# DMX.net
KiCad netlist of a schematic drawn in Altium Designer
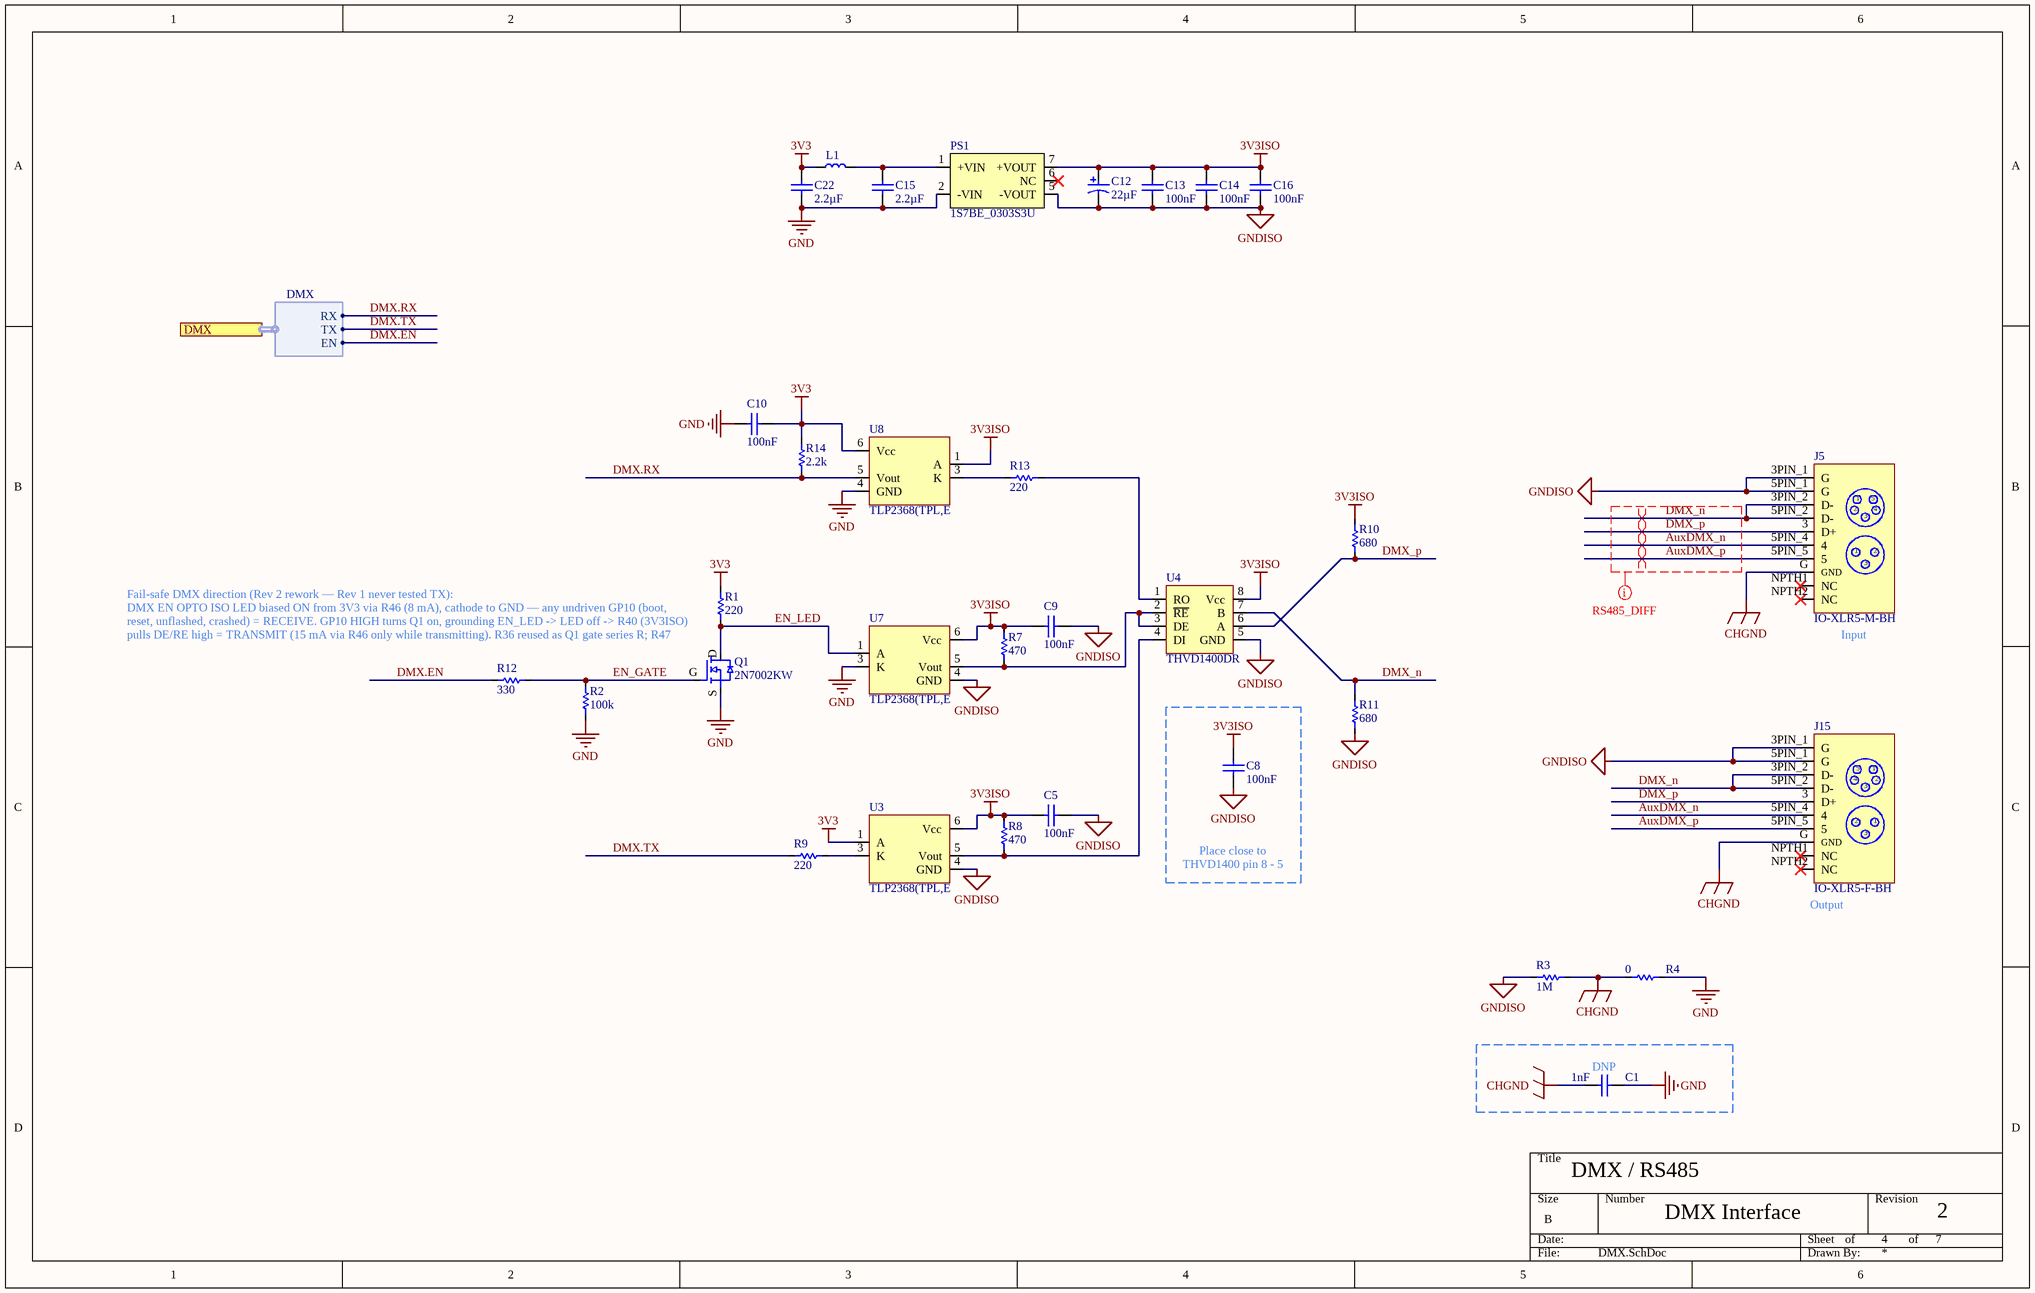
[diagram p0: DMX.SchDoc]

(export (version "E")
  (design (tool "Eeschema 10.0.6"))
  (components
    (comp (ref "C1")
      (value "1nF")
      (footprint "CAPC1608X10N_0603_MED")
      (fields (field (name "TOLERANCE") "10%") (field (name "Comment") "C0603C102K5RACTU"))
      (libsource (lib "Equus Computer Systems") (part "CAP-NP-2"))
    )
    (comp (ref "C5")
      (value "100nF")
      (footprint "CAPC1608X10N_0603_MED")
      (fields (field (name "Comment") "CC0603KRX7R0BB104"))
      (libsource (lib "Equus Computer Systems") (part "CAP-NP-2"))
    )
    (comp (ref "C8")
      (value "100nF")
      (footprint "CAPC1608X10N_0603_MED")
      (fields (field (name "Comment") "CC0603KRX7R0BB104"))
      (libsource (lib "Equus Computer Systems") (part "CAP-NP-2"))
    )
    (comp (ref "C9")
      (value "100nF")
      (footprint "CAPC1608X10N_0603_MED")
      (fields (field (name "Comment") "CC0603KRX7R0BB104"))
      (libsource (lib "Equus Computer Systems") (part "CAP-NP-2"))
    )
    (comp (ref "C10")
      (value "100nF")
      (footprint "CAPC1608X10N_0603_MED")
      (fields (field (name "Comment") "CC0603KRX7R0BB104"))
      (libsource (lib "Equus Computer Systems") (part "CAP-NP-2"))
    )
    (comp (ref "C12")
      (value "22µF")
      (footprint "CAPCP3528X21N_1210_1411_MED")
      (fields (field (name "TOLERANCE") "10%") (field (name "Comment") "TPSB226K010R0500"))
      (libsource (lib "Equus Computer Systems") (part "CAP-P-2"))
    )
    (comp (ref "C13")
      (value "100nF")
      (footprint "CAPC1608X10N_0603_MED")
      (fields (field (name "Comment") "CC0603KRX7R0BB104"))
      (libsource (lib "Equus Computer Systems") (part "CAP-NP-2"))
    )
    (comp (ref "C14")
      (value "100nF")
      (footprint "CAPC1608X10N_0603_MED")
      (fields (field (name "Comment") "CC0603KRX7R0BB104"))
      (libsource (lib "Equus Computer Systems") (part "CAP-NP-2"))
    )
    (comp (ref "C15")
      (value "2.2µF")
      (footprint "CAPC2012X14N_0805_MED")
      (description "Ceramic Capacitor, Multilayer, Ceramic, 2.2uF, 50V, 10%, X6S, 0805")
      (fields (field (name "TOLERANCE") "10%") (field (name "Comment") "CGA4J3X7R1H225K125AE"))
      (libsource (lib "Equus Computer Systems") (part "CAP-NP-2"))
    )
    (comp (ref "C16")
      (value "100nF")
      (footprint "CAPC1608X10N_0603_MED")
      (fields (field (name "Comment") "CC0603KRX7R0BB104"))
      (libsource (lib "Equus Computer Systems") (part "CAP-NP-2"))
    )
    (comp (ref "C22")
      (value "2.2µF")
      (footprint "CAPC2012X14N_0805_MED")
      (description "Ceramic Capacitor, Multilayer, Ceramic, 2.2uF, 50V, 10%, X6S, 0805")
      (fields (field (name "TOLERANCE") "10%") (field (name "Comment") "CGA4J3X7R1H225K125AE"))
      (libsource (lib "Equus Computer Systems") (part "CAP-NP-2"))
    )
    (comp (ref "J5")
      (value "IO-XLR5-M-BH")
      (footprint "IO-XLR5-M-BH-Footprint-1")
      (description "B Series, 5 Pin XLR, Male, Horizontal Pcb Mount With Separate Ground Pin")
      (libsource (lib "Equus Computer Systems") (part "XLR5-M"))
    )
    (comp (ref "J15")
      (value "IO-XLR5-F-BH")
      (footprint "IO-XLR5-F-BH-Footprint-1")
      (description "B-Series 5-Pin XLR Female Horizontal PCB Mount with Separate Ground-Pin Metal Face Plate")
      (libsource (lib "Equus Computer Systems") (part "XLR5-F"))
    )
    (comp (ref "L1")
      (value "SRR6038-180Y")
      (footprint "IND_SRR6038-180Y")
      (description "General Purpose Inductor, 18uH, 30%, 1 Element, Ferrite-Core, SMD, 2727")
      (fields (field (name "TOLERANCE") "30%"))
      (libsource (lib "Equus Computer Systems") (part "IND-2"))
    )
    (comp (ref "PS1")
      (value "1S7BE_0303S3U")
      (footprint "CONV_1S7BE_0303S3U")
      (description "ISOLATED MODULE DC DC CONVERTERS")
      (fields (field (name "MF") "Gaptec"))
      (libsource (lib "Equus Computer Systems") (part "1S7BE_0303S3U"))
    )
    (comp (ref "Q1")
      (value "2N7002KW")
      (footprint "ONSEMI_SOT65P210X110-3N")
      (libsource (lib "Equus Computer Systems") (part "TRANS-MOSFET"))
    )
    (comp (ref "R1")
      (value "220")
      (footprint "RESC1608X06N_0603_MED")
      (fields
        (field (name "POWER") "100mW")
        (field (name "TOLERANCE") "1%")
        (field (name "Comment") "RC0603FR-07220RL")
      )
      (libsource (lib "Equus Computer Systems") (part "RES-2"))
    )
    (comp (ref "R2")
      (value "100k")
      (footprint "RESC1608X06N_0603_MED")
      (fields
        (field (name "POWER") "100mW")
        (field (name "TOLERANCE") "0.5%")
        (field (name "Comment") "RC0603DR-07100KL")
      )
      (libsource (lib "Equus Computer Systems") (part "RES-2"))
    )
    (comp (ref "R3")
      (value "1M")
      (footprint "RESC1608X06N_0603_MED")
      (description "Fixed Resistor, Metal Glaze/thick Film, 0.1W, 1Mohm,")
      (fields (field (name "TOLERANCE") "1%") (field (name "POWER") "100mW"))
      (libsource (lib "Equus Computer Systems") (part "RES-2"))
    )
    (comp (ref "R4")
      (value "0")
      (footprint "RESC1608X06N_0603_MED")
      (description "RC Series 0603 0.1 W 0 Ohm Jumper Surface Mount Thick Film Chip Resistor")
      (fields (field (name "POWER") "100mW") (field (name "TOLERANCE") "1%"))
      (libsource (lib "Equus Computer Systems") (part "RES-2"))
    )
    (comp (ref "R7")
      (value "470")
      (footprint "RESC1608X06N_0603_MED")
      (fields
        (field (name "TOLERANCE") "1%")
        (field (name "POWER") "100mW")
        (field (name "Comment") "RC0603FR-07470RL")
      )
      (libsource (lib "Equus Computer Systems") (part "RES-2"))
    )
    (comp (ref "R8")
      (value "470")
      (footprint "RESC1608X06N_0603_MED")
      (fields
        (field (name "TOLERANCE") "1%")
        (field (name "POWER") "100mW")
        (field (name "Comment") "RC0603FR-07470RL")
      )
      (libsource (lib "Equus Computer Systems") (part "RES-2"))
    )
    (comp (ref "R9")
      (value "220")
      (footprint "RESC1608X06N_0603_MED")
      (fields
        (field (name "POWER") "100mW")
        (field (name "TOLERANCE") "1%")
        (field (name "Comment") "RC0603FR-07220RL")
      )
      (libsource (lib "Equus Computer Systems") (part "RES-2"))
    )
    (comp (ref "R10")
      (value "680")
      (footprint "RESC1608X06N_0603_MED")
      (fields
        (field (name "TOLERANCE") "1%")
        (field (name "POWER") "100mW")
        (field (name "Comment") "RC0603FR-07680RL")
      )
      (libsource (lib "Equus Computer Systems") (part "RES-2"))
    )
    (comp (ref "R11")
      (value "680")
      (footprint "RESC1608X06N_0603_MED")
      (fields
        (field (name "TOLERANCE") "1%")
        (field (name "POWER") "100mW")
        (field (name "Comment") "RC0603FR-07680RL")
      )
      (libsource (lib "Equus Computer Systems") (part "RES-2"))
    )
    (comp (ref "R12")
      (value "330")
      (footprint "RESC1608X06N_0603_MED")
      (fields
        (field (name "POWER") "100mW")
        (field (name "TOLERANCE") "1%")
        (field (name "Comment") "RC0603FR-07330RL")
      )
      (libsource (lib "Equus Computer Systems") (part "RES-2"))
    )
    (comp (ref "R13")
      (value "220")
      (footprint "RESC1608X06N_0603_MED")
      (fields
        (field (name "TOLERANCE") "1%")
        (field (name "POWER") "100mW")
        (field (name "Comment") "RC0603FR-07220RL")
      )
      (libsource (lib "Equus Computer Systems") (part "RES-2"))
    )
    (comp (ref "R14")
      (value "2.2k")
      (footprint "RESC1608X06N_0603_MED")
      (fields
        (field (name "TOLERANCE") "1%")
        (field (name "POWER") "100mW")
        (field (name "Comment") "RC0603FR-072K2L")
      )
      (libsource (lib "Equus Computer Systems") (part "RES-2"))
    )
    (comp (ref "U3")
      (value "TLP2368(TPL,E")
      (footprint "SOT125P700X220-5N")
      (description "Logic IC Output Optocoupler, 1-Channel, 1-Element, 3750V Isolation, 20MBps")
      (libsource (lib "") (part "TLP2368-Symbol-1_1"))
    )
    (comp (ref "U4")
      (value "THVD1400DR")
      (footprint "SOIC127P600X175-8N")
      (description "Line Transceiver, 1 Func, 1 Driver, 1 Rcvr, PDSO8")
      (libsource (lib "Equus Computer Systems") (part "THVD1400DR"))
    )
    (comp (ref "U7")
      (value "TLP2368(TPL,E")
      (footprint "SOT125P700X220-5N")
      (description "Logic IC Output Optocoupler, 1-Channel, 1-Element, 3750V Isolation, 20MBps")
      (libsource (lib "") (part "TLP2368-Symbol-1_1"))
    )
    (comp (ref "U8")
      (value "TLP2368(TPL,E")
      (footprint "SOT125P700X220-5N")
      (description "Logic IC Output Optocoupler, 1-Channel, 1-Element, 3750V Isolation, 20MBps")
      (libsource (lib "Equus Computer Systems") (part "TLP2368-Symbol-1"))
    )
  )
  (nets
    (net (code "2") (name "/AuxDMX_n") (class "Default")
      (node (ref "J15") (pin "5PIN_4") (pinfunction "4_5PIN_4") (pintype "passive"))
      (node (ref "J5") (pin "5PIN_4") (pinfunction "4_5PIN_4") (pintype "passive"))
    )
    (net (code "3") (name "/AuxDMX_p") (class "Default")
      (node (ref "J15") (pin "5PIN_5") (pinfunction "5_5PIN_5") (pintype "passive"))
      (node (ref "J5") (pin "5PIN_5") (pinfunction "5_5PIN_5") (pintype "passive"))
    )
    (net (code "4") (name "/DMX.EN") (class "Default")
      (node (ref "R12") (pin "1") (pinfunction "1_1") (pintype "passive"))
    )
    (net (code "5") (name "/DMX.RX") (class "Default")
      (node (ref "R14") (pin "1") (pinfunction "1_1") (pintype "passive"))
      (node (ref "U8") (pin "5") (pinfunction "Vout_5") (pintype "passive"))
    )
    (net (code "6") (name "/DMX.TX") (class "Default")
      (node (ref "R9") (pin "1") (pinfunction "1_1") (pintype "passive"))
    )
    (net (code "7") (name "/DMX_n") (class "Default")
      (node (ref "J15") (pin "3PIN_2") (pinfunction "D-_3PIN_2") (pintype "passive"))
      (node (ref "J15") (pin "5PIN_2") (pinfunction "D-_5PIN_2") (pintype "passive"))
      (node (ref "J5") (pin "3PIN_2") (pinfunction "D-_3PIN_2") (pintype "passive"))
      (node (ref "J5") (pin "5PIN_2") (pinfunction "D-_5PIN_2") (pintype "passive"))
      (node (ref "R11") (pin "2") (pinfunction "2_2") (pintype "passive"))
      (node (ref "U4") (pin "7") (pinfunction "B_7") (pintype "passive"))
    )
    (net (code "8") (name "/DMX_p") (class "Default")
      (node (ref "J15") (pin "3") (pinfunction "D+_3") (pintype "passive"))
      (node (ref "J5") (pin "3") (pinfunction "D+_3") (pintype "passive"))
      (node (ref "R10") (pin "1") (pinfunction "1_1") (pintype "passive"))
      (node (ref "U4") (pin "6") (pinfunction "A_6") (pintype "passive"))
    )
    (net (code "9") (name "/EN_GATE") (class "Default")
      (node (ref "Q1") (pin "G") (pinfunction "G_G") (pintype "passive"))
      (node (ref "R12") (pin "2") (pinfunction "2_2") (pintype "passive"))
      (node (ref "R2") (pin "2") (pinfunction "2_2") (pintype "passive"))
    )
    (net (code "10") (name "/EN_LED") (class "Default")
      (node (ref "Q1") (pin "D") (pinfunction "D_D") (pintype "passive"))
      (node (ref "R1") (pin "1") (pinfunction "1_1") (pintype "passive"))
      (node (ref "U7") (pin "1") (pinfunction "A_1") (pintype "passive"))
    )
    (net (code "12") (name "3V3") (class "Default")
      (node (ref "C10") (pin "1") (pinfunction "1_1") (pintype "passive"))
      (node (ref "C22") (pin "2") (pinfunction "2_2") (pintype "passive"))
      (node (ref "L1") (pin "1") (pinfunction "1_1") (pintype "passive"))
      (node (ref "R1") (pin "2") (pinfunction "2_2") (pintype "passive"))
      (node (ref "R14") (pin "2") (pinfunction "2_2") (pintype "passive"))
      (node (ref "U3") (pin "1") (pinfunction "A_1") (pintype "passive"))
      (node (ref "U8") (pin "6") (pinfunction "Vcc_6") (pintype "passive"))
    )
    (net (code "13") (name "3V3ISO") (class "Default")
      (node (ref "C12") (pin "1") (pinfunction "1_1") (pintype "passive"))
      (node (ref "C13") (pin "2") (pinfunction "2_2") (pintype "passive"))
      (node (ref "C14") (pin "2") (pinfunction "2_2") (pintype "passive"))
      (node (ref "C16") (pin "2") (pinfunction "2_2") (pintype "passive"))
      (node (ref "C5") (pin "2") (pinfunction "2_2") (pintype "passive"))
      (node (ref "C8") (pin "1") (pinfunction "1_1") (pintype "passive"))
      (node (ref "C9") (pin "2") (pinfunction "2_2") (pintype "passive"))
      (node (ref "PS1") (pin "7") (pinfunction "+VOUT_7") (pintype "passive"))
      (node (ref "R10") (pin "2") (pinfunction "2_2") (pintype "passive"))
      (node (ref "R7") (pin "2") (pinfunction "2_2") (pintype "passive"))
      (node (ref "R8") (pin "2") (pinfunction "2_2") (pintype "passive"))
      (node (ref "U3") (pin "6") (pinfunction "Vcc_6") (pintype "passive"))
      (node (ref "U4") (pin "8") (pinfunction "Vcc_8") (pintype "passive"))
      (node (ref "U7") (pin "6") (pinfunction "Vcc_6") (pintype "passive"))
      (node (ref "U8") (pin "1") (pinfunction "A_1") (pintype "passive"))
    )
    (net (code "14") (name "CHGND") (class "Default")
      (node (ref "C1") (pin "1") (pinfunction "1_1") (pintype "passive"))
      (node (ref "J15") (pin "G") (pinfunction "GND_G") (pintype "passive"))
      (node (ref "J5") (pin "G") (pinfunction "GND_G") (pintype "passive"))
      (node (ref "R3") (pin "2") (pinfunction "2_2") (pintype "passive"))
      (node (ref "R4") (pin "1") (pinfunction "1_1") (pintype "passive"))
    )
    (net (code "15") (name "GND") (class "Default")
      (node (ref "C1") (pin "2") (pinfunction "2_2") (pintype "passive"))
      (node (ref "C10") (pin "2") (pinfunction "2_2") (pintype "passive"))
      (node (ref "C15") (pin "1") (pinfunction "1_1") (pintype "passive"))
      (node (ref "C22") (pin "1") (pinfunction "1_1") (pintype "passive"))
      (node (ref "PS1") (pin "2") (pinfunction "-VIN_2") (pintype "passive"))
      (node (ref "Q1") (pin "S") (pinfunction "S_S") (pintype "passive"))
      (node (ref "R2") (pin "1") (pinfunction "1_1") (pintype "passive"))
      (node (ref "R4") (pin "2") (pinfunction "2_2") (pintype "passive"))
      (node (ref "U7") (pin "3") (pinfunction "K_3") (pintype "passive"))
      (node (ref "U8") (pin "4") (pinfunction "GND_4") (pintype "passive"))
    )
    (net (code "16") (name "GNDISO") (class "Default")
      (node (ref "C12") (pin "2") (pinfunction "2_2") (pintype "passive"))
      (node (ref "C13") (pin "1") (pinfunction "1_1") (pintype "passive"))
      (node (ref "C14") (pin "1") (pinfunction "1_1") (pintype "passive"))
      (node (ref "C16") (pin "1") (pinfunction "1_1") (pintype "passive"))
      (node (ref "C5") (pin "1") (pinfunction "1_1") (pintype "passive"))
      (node (ref "C8") (pin "2") (pinfunction "2_2") (pintype "passive"))
      (node (ref "C9") (pin "1") (pinfunction "1_1") (pintype "passive"))
      (node (ref "J15") (pin "3PIN_1") (pinfunction "G_3PIN_1") (pintype "passive"))
      (node (ref "J15") (pin "5PIN_1") (pinfunction "G_5PIN_1") (pintype "passive"))
      (node (ref "J5") (pin "3PIN_1") (pinfunction "G_3PIN_1") (pintype "passive"))
      (node (ref "J5") (pin "5PIN_1") (pinfunction "G_5PIN_1") (pintype "passive"))
      (node (ref "PS1") (pin "5") (pinfunction "-VOUT_5") (pintype "passive"))
      (node (ref "R11") (pin "1") (pinfunction "1_1") (pintype "passive"))
      (node (ref "R3") (pin "1") (pinfunction "1_1") (pintype "passive"))
      (node (ref "U3") (pin "4") (pinfunction "GND_4") (pintype "passive"))
      (node (ref "U4") (pin "5") (pinfunction "GND_5") (pintype "passive"))
      (node (ref "U7") (pin "4") (pinfunction "GND_4") (pintype "passive"))
    )
    (net (code "17") (name "Net-(PS1-+VIN)") (class "Default")
      (node (ref "C15") (pin "2") (pinfunction "2_2") (pintype "passive"))
      (node (ref "L1") (pin "2") (pinfunction "2_2") (pintype "passive"))
      (node (ref "PS1") (pin "1") (pinfunction "+VIN_1") (pintype "passive"))
    )
    (net (code "18") (name "Net-(U3-K)") (class "Default")
      (node (ref "R9") (pin "2") (pinfunction "2_2") (pintype "passive"))
      (node (ref "U3") (pin "3") (pinfunction "K_3") (pintype "passive"))
    )
    (net (code "19") (name "Net-(U3-Vout)") (class "Default")
      (node (ref "R8") (pin "1") (pinfunction "1_1") (pintype "passive"))
      (node (ref "U3") (pin "5") (pinfunction "Vout_5") (pintype "passive"))
      (node (ref "U4") (pin "4") (pinfunction "DI_4") (pintype "passive"))
    )
    (net (code "20") (name "Net-(U4-DE)") (class "Default")
      (node (ref "R7") (pin "1") (pinfunction "1_1") (pintype "passive"))
      (node (ref "U4") (pin "2") (pinfunction "~{RE}_2") (pintype "passive"))
      (node (ref "U4") (pin "3") (pinfunction "DE_3") (pintype "passive"))
      (node (ref "U7") (pin "5") (pinfunction "Vout_5") (pintype "passive"))
    )
    (net (code "21") (name "Net-(U4-RO)") (class "Default")
      (node (ref "R13") (pin "2") (pinfunction "2_2") (pintype "passive"))
      (node (ref "U4") (pin "1") (pinfunction "RO_1") (pintype "passive"))
    )
    (net (code "22") (name "Net-(U8-K)") (class "Default")
      (node (ref "R13") (pin "1") (pinfunction "1_1") (pintype "passive"))
      (node (ref "U8") (pin "3") (pinfunction "K_3") (pintype "passive"))
    )
    (net (code "23") (name "unconnected-(J5-NC-PadNPTH1)") (class "Default")
      (node (ref "J5") (pin "NPTH1") (pinfunction "NC_NPTH1") (pintype "passive+no_connect"))
    )
    (net (code "24") (name "unconnected-(J5-NC-PadNPTH2)") (class "Default")
      (node (ref "J5") (pin "NPTH2") (pinfunction "NC_NPTH2") (pintype "passive+no_connect"))
    )
    (net (code "25") (name "unconnected-(J15-NC-PadNPTH1)") (class "Default")
      (node (ref "J15") (pin "NPTH1") (pinfunction "NC_NPTH1") (pintype "passive+no_connect"))
    )
    (net (code "26") (name "unconnected-(J15-NC-PadNPTH2)") (class "Default")
      (node (ref "J15") (pin "NPTH2") (pinfunction "NC_NPTH2") (pintype "passive+no_connect"))
    )
    (net (code "27") (name "unconnected-(PS1-NC-Pad6)") (class "Default")
      (node (ref "PS1") (pin "6") (pinfunction "NC_6") (pintype "passive+no_connect"))
    )
  )
)
